# Power_sheet.net
KiCad netlist of a schematic drawn in Altium Designer
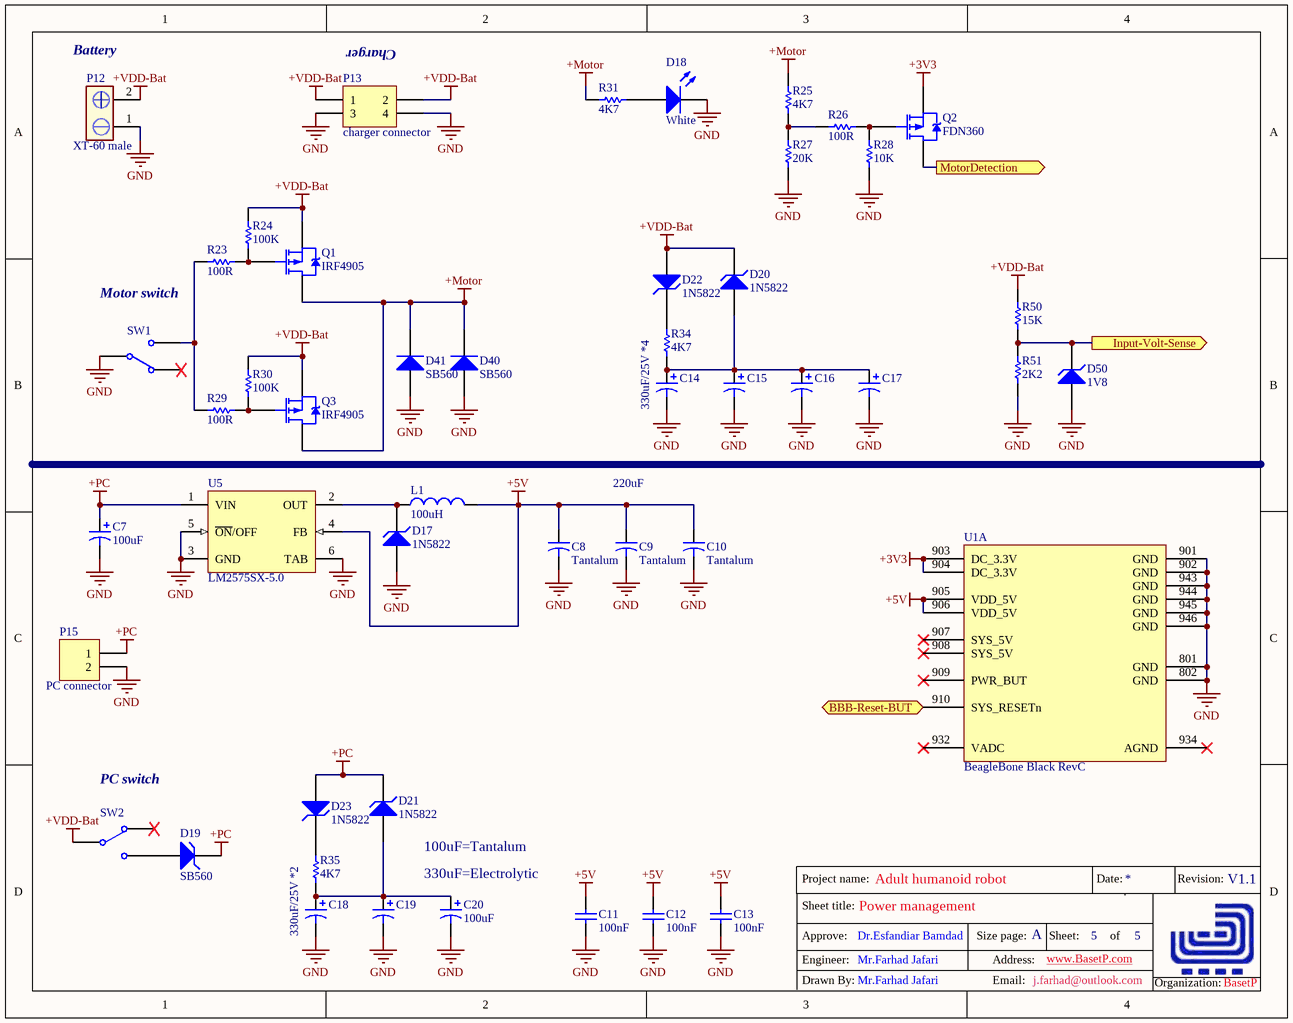
[diagram p0: Power sheet.SchDoc]

(export (version "E")
  (design (tool "Eeschema 10.0.6"))
  (components
    (comp (ref "C7")
      (value "100uF")
      (footprint "B")
      (description "Solid Aluminum Capacitor with Organic Semiconductor Electrolyte: 10uF, 10V, Bulk Pack")
      (fields (field (name "PUBLISHER") "Altium Limited"))
      (libsource (lib "Farhad_Library") (part "100uF/25V"))
    )
    (comp (ref "C8")
      (value "Tantalum")
      (footprint "tantalum E")
      (libsource (lib "Farhad_Library") (part "Tantalum"))
    )
    (comp (ref "C9")
      (value "Tantalum")
      (footprint "tantalum E")
      (libsource (lib "Farhad_Library") (part "Tantalum"))
    )
    (comp (ref "C10")
      (value "Tantalum")
      (footprint "tantalum E")
      (libsource (lib "Farhad_Library") (part "Tantalum"))
    )
    (comp (ref "C11")
      (value "100nF")
      (footprint "0805")
      (description "Ceramic Chip Capacitor - Standard")
      (fields (field (name "Comment") "C0805") (field (name "PUBLISHER") "Altium Limited"))
      (libsource (lib "KEMET Chip Capacitor") (part "C0805"))
    )
    (comp (ref "C12")
      (value "100nF")
      (footprint "0805")
      (description "Ceramic Chip Capacitor - Standard")
      (fields (field (name "Comment") "C0805") (field (name "PUBLISHER") "Altium Limited"))
      (libsource (lib "KEMET Chip Capacitor") (part "C0805"))
    )
    (comp (ref "C13")
      (value "100nF")
      (footprint "0805")
      (description "Ceramic Chip Capacitor - Standard")
      (fields (field (name "Comment") "C0805") (field (name "PUBLISHER") "Altium Limited"))
      (libsource (lib "KEMET Chip Capacitor") (part "C0805"))
    )
    (comp (ref "C14")
      (value "330uF/25V *4")
      (footprint "E'")
      (description "Solid Aluminum Capacitor with Organic Semiconductor Electrolyte: 100uF, 6.3V, Bulk Pack")
      (fields (field (name "PUBLISHER") "Altium Limited"))
      (libsource (lib "Farhad_Library") (part "330uF/25V"))
    )
    (comp (ref "C15")
      (value "330uF/25V")
      (footprint "E'")
      (description "Solid Aluminum Capacitor with Organic Semiconductor Electrolyte: 100uF, 6.3V, Bulk Pack")
      (fields (field (name "PUBLISHER") "Altium Limited"))
      (libsource (lib "Farhad_Library") (part "330uF/25V"))
    )
    (comp (ref "C16")
      (value "330uF/25V")
      (footprint "E'")
      (description "Solid Aluminum Capacitor with Organic Semiconductor Electrolyte: 100uF, 6.3V, Bulk Pack")
      (fields (field (name "PUBLISHER") "Altium Limited"))
      (libsource (lib "Farhad_Library") (part "330uF/25V"))
    )
    (comp (ref "C17")
      (value "330uF/25V")
      (footprint "E'")
      (description "Solid Aluminum Capacitor with Organic Semiconductor Electrolyte: 100uF, 6.3V, Bulk Pack")
      (fields (field (name "PUBLISHER") "Altium Limited"))
      (libsource (lib "Farhad_Library") (part "330uF/25V"))
    )
    (comp (ref "C18")
      (value "330uF/25V *2")
      (footprint "E'")
      (description "Solid Aluminum Capacitor with Organic Semiconductor Electrolyte: 100uF, 6.3V, Bulk Pack")
      (fields (field (name "PUBLISHER") "Altium Limited"))
      (libsource (lib "Farhad_Library") (part "330uF/25V"))
    )
    (comp (ref "C19")
      (value "`")
      (footprint "E'")
      (description "Solid Aluminum Capacitor with Organic Semiconductor Electrolyte: 100uF, 6.3V, Bulk Pack")
      (fields (field (name "PUBLISHER") "Altium Limited"))
      (libsource (lib "Farhad_Library") (part "330uF/25V"))
    )
    (comp (ref "C20")
      (value "100uF")
      (footprint "C5")
      (fields (field (name "PUBLISHER") "Altium Limited"))
      (libsource (lib "Vishay Sprague Tantalum Radial-Lead Capacitor") (part "STC68-15C5RM"))
    )
    (comp (ref "D17")
      (value "1N5822")
      (footprint "DL-41")
      (description "High-Voltage Power schottky Diode")
      (fields (field (name "PUBLISHER") "Altium Limited"))
      (libsource (lib "Farhad_Library") (part "1N5822"))
    )
    (comp (ref "D18")
      (value "White")
      (footprint "LED Red-0805")
      (description "High Performance Chip LED, Amber")
      (fields (field (name "PUBLISHER") "Altium Limited"))
      (libsource (lib "Farhad_Library") (part "LED-RED"))
    )
    (comp (ref "D19")
      (value "SB560")
      (footprint "DL-41")
      (description "High-Voltage Power schottky Diode")
      (fields (field (name "PUBLISHER") "Altium Limited"))
      (libsource (lib "Farhad_Library") (part "1N5822"))
    )
    (comp (ref "D20")
      (value "1N5822")
      (footprint "MELF")
      (description "High-Voltage Power Zener Diode")
      (fields (field (name "PUBLISHER") "Altium Limited"))
      (libsource (lib "Vishay Lite-On Discrete Diode") (part "ZMU100"))
    )
    (comp (ref "D21")
      (value "1N5822")
      (footprint "MELF")
      (description "High-Voltage Power Zener Diode")
      (fields (field (name "PUBLISHER") "Altium Limited"))
      (libsource (lib "Vishay Lite-On Discrete Diode") (part "ZMU100"))
    )
    (comp (ref "D22")
      (value "1N5822")
      (footprint "MELF")
      (description "High-Voltage Power Zener Diode")
      (fields (field (name "PUBLISHER") "Altium Limited"))
      (libsource (lib "Vishay Lite-On Discrete Diode") (part "ZMU100"))
    )
    (comp (ref "D23")
      (value "1N5822")
      (footprint "MELF")
      (description "High-Voltage Power Zener Diode")
      (fields (field (name "PUBLISHER") "Altium Limited"))
      (libsource (lib "Vishay Lite-On Discrete Diode") (part "ZMU100"))
    )
    (comp (ref "D40")
      (value "SB560")
      (footprint "DO-41")
      (description "1 Amp General Purpose Rectifier")
      (fields (field (name "PUBLISHER") "Altium Limited"))
      (libsource (lib "Farhad_Library") (part "Diode SB560"))
    )
    (comp (ref "D41")
      (value "SB560")
      (footprint "DO-41")
      (description "1 Amp General Purpose Rectifier")
      (fields (field (name "PUBLISHER") "Altium Limited"))
      (libsource (lib "Farhad_Library") (part "Diode SB560"))
    )
    (comp (ref "D50")
      (value "1V8")
      (footprint "MELF")
      (description "High-Voltage Power Zener Diode")
      (fields (field (name "PUBLISHER") "Altium Limited"))
      (libsource (lib "Vishay Lite-On Discrete Diode") (part "ZMU100"))
    )
    (comp (ref "L1")
      (value "100uH")
      (footprint "inductor coil")
      (description "Inductor coil  17mm * 9mm")
      (fields (field (name "PUBLISHER") "Altium Limited"))
      (libsource (lib "Farhad_Library") (part "Inductor coil"))
    )
    (comp (ref "P12")
      (value "XT-60 male")
      (footprint "XT-60 connector")
      (description "XT-60 connector male for battery")
      (libsource (lib "Farhad_Library") (part "XT-60 connector male"))
    )
    (comp (ref "P13")
      (value "charger connector")
      (footprint "connector 2*2")
      (description "Header, 4-Pin, 2X2 right angle")
      (fields (field (name "PUBLISHER") "Altium Limited"))
      (libsource (lib "Farhad_Library") (part "Header 2X2 right angle"))
    )
    (comp (ref "P15")
      (value "PC connector")
      (footprint "connector 1*2")
      (description "Header, 2-Pin right angle")
      (fields (field (name "PUBLISHER") "Altium Limited"))
      (libsource (lib "Farhad_Library") (part "Header 2 right angle"))
    )
    (comp (ref "Q1")
      (value "IRF4905")
      (footprint "TO-220AB")
      (description "HEXFET Power MOSFET")
      (fields (field (name "PUBLISHER") "Altium Limited"))
      (libsource (lib "IR Discrete MOSFET - Power") (part "IRF4905"))
    )
    (comp (ref "Q2")
      (value "FDN360")
      (footprint "SOT-23B_L")
      (description "Mosfet")
      (libsource (lib "Farhad_Library") (part "FDN360P"))
    )
    (comp (ref "Q3")
      (value "IRF4905")
      (footprint "TO-220AB")
      (description "HEXFET Power MOSFET")
      (fields (field (name "PUBLISHER") "Altium Limited"))
      (libsource (lib "IR Discrete MOSFET - Power") (part "IRF4905"))
    )
    (comp (ref "R23")
      (value "100R")
      (footprint "6-0805")
      (fields (field (name "PUBLISHER") "Altium Limited"))
      (libsource (lib "Panasonic Resistor") (part "ERJ6RS"))
    )
    (comp (ref "R24")
      (value "100K")
      (footprint "6-0805")
      (fields (field (name "PUBLISHER") "Altium Limited"))
      (libsource (lib "Panasonic Resistor") (part "ERJ6RS"))
    )
    (comp (ref "R25")
      (value "4K7")
      (footprint "6-0805")
      (fields (field (name "PUBLISHER") "Altium Limited"))
      (libsource (lib "Panasonic Resistor") (part "ERJ6RS"))
    )
    (comp (ref "R26")
      (value "100R")
      (footprint "6-0805")
      (fields (field (name "PUBLISHER") "Altium Limited"))
      (libsource (lib "Panasonic Resistor") (part "ERJ6RS"))
    )
    (comp (ref "R27")
      (value "20K")
      (footprint "6-0805")
      (fields (field (name "PUBLISHER") "Altium Limited"))
      (libsource (lib "Panasonic Resistor") (part "ERJ6RS"))
    )
    (comp (ref "R28")
      (value "10K")
      (footprint "6-0805")
      (fields (field (name "PUBLISHER") "Altium Limited"))
      (libsource (lib "Panasonic Resistor") (part "ERJ6RS"))
    )
    (comp (ref "R29")
      (value "100R")
      (footprint "6-0805")
      (fields (field (name "PUBLISHER") "Altium Limited"))
      (libsource (lib "Panasonic Resistor") (part "ERJ6RS"))
    )
    (comp (ref "R30")
      (value "100K")
      (footprint "6-0805")
      (fields (field (name "PUBLISHER") "Altium Limited"))
      (libsource (lib "Panasonic Resistor") (part "ERJ6RS"))
    )
    (comp (ref "R31")
      (value "4K7")
      (footprint "6-0805")
      (fields (field (name "PUBLISHER") "Altium Limited"))
      (libsource (lib "Panasonic Resistor") (part "ERJ6RS"))
    )
    (comp (ref "R34")
      (value "4K7")
      (footprint "8RB-1206")
      (fields (field (name "PUBLISHER") "Altium Limited"))
      (libsource (lib "Panasonic Resistor") (part "ERJ8RS"))
    )
    (comp (ref "R35")
      (value "4K7")
      (footprint "8RB-1206")
      (fields (field (name "PUBLISHER") "Altium Limited"))
      (libsource (lib "Panasonic Resistor") (part "ERJ8RS"))
    )
    (comp (ref "R50")
      (value "15K")
      (footprint "6-0805")
      (fields (field (name "PUBLISHER") "Altium Limited"))
      (libsource (lib "Panasonic Resistor") (part "ERJ6RS"))
    )
    (comp (ref "R51")
      (value "2K2")
      (footprint "6-0805")
      (fields (field (name "PUBLISHER") "Altium Limited"))
      (libsource (lib "Panasonic Resistor") (part "ERJ6RS"))
    )
    (comp (ref "SW1")
      (value "switch Red")
      (footprint "SW-power3A")
      (description "switch power black 3A/250VAC")
      (libsource (lib "Farhad_Library") (part "switch Power"))
    )
    (comp (ref "SW2")
      (value "switch Red")
      (footprint "SW-power3A")
      (description "switch power black 3A/250VAC")
      (libsource (lib "Farhad_Library") (part "switch Power"))
    )
    (comp (ref "U1")
      (value "BeagleBone Black RevC")
      (footprint "BBB-C")
      (libsource (lib "Farhad_Library") (part "BeagleBoneBlackRevC"))
    )
    (comp (ref "U5")
      (value "LM2575SX-5.0")
      (footprint "TS5B_N")
      (description "SIMPLE SWITCHER® 3A Step-Down Voltage Regulator, 5-pin TO-263")
      (fields
        (field (name "PARTNUMBER") "LM2576SX-5.0")
        (field (name "MANUFACTURER") "National Semiconductor")
        (field (name "PUBLISHER") "Altium Limited")
      )
      (libsource (lib "NSC Switcher") (part "LM2576SX-5.0"))
    )
  )
  (nets
    (net (code "1") (name "+3V3") (class "Default")
      (node (ref "Q2") (pin "2") (pinfunction "S_2") (pintype "passive"))
      (node (ref "U1") (pin "903") (pinfunction "DC_3.3V_903") (pintype "passive"))
      (node (ref "U1") (pin "904") (pinfunction "DC_3.3V_904") (pintype "passive"))
    )
    (net (code "2") (name "+5V") (class "Default")
      (node (ref "C10") (pin "1") (pinfunction "1_1") (pintype "passive"))
      (node (ref "C11") (pin "2") (pinfunction "2_2") (pintype "passive"))
      (node (ref "C12") (pin "2") (pinfunction "2_2") (pintype "passive"))
      (node (ref "C13") (pin "2") (pinfunction "2_2") (pintype "passive"))
      (node (ref "C8") (pin "1") (pinfunction "1_1") (pintype "passive"))
      (node (ref "C9") (pin "1") (pinfunction "1_1") (pintype "passive"))
      (node (ref "L1") (pin "2") (pinfunction "2_2") (pintype "passive"))
      (node (ref "U1") (pin "905") (pinfunction "VDD_5V_905") (pintype "passive"))
      (node (ref "U1") (pin "906") (pinfunction "VDD_5V_906") (pintype "passive"))
      (node (ref "U5") (pin "4") (pinfunction "FB_4") (pintype "input"))
    )
    (net (code "3") (name "+Motor") (class "Default")
      (node (ref "D40") (pin "2") (pinfunction "K_2") (pintype "passive"))
      (node (ref "D41") (pin "2") (pinfunction "K_2") (pintype "passive"))
      (node (ref "Q1") (pin "2") (pinfunction "D_2") (pintype "passive"))
      (node (ref "Q3") (pin "2") (pinfunction "D_2") (pintype "passive"))
      (node (ref "R25") (pin "2") (pinfunction "2_2") (pintype "passive"))
      (node (ref "R31") (pin "1") (pinfunction "1_1") (pintype "passive"))
    )
    (net (code "4") (name "+PC") (class "Default")
      (node (ref "C7") (pin "1") (pinfunction "1_1") (pintype "passive"))
      (node (ref "D19") (pin "2") (pinfunction "K_2") (pintype "passive"))
      (node (ref "D21") (pin "2") (pinfunction "K_2") (pintype "passive"))
      (node (ref "D23") (pin "1") (pinfunction "A_1") (pintype "passive"))
      (node (ref "P15") (pin "1") (pinfunction "1_1") (pintype "passive"))
      (node (ref "U5") (pin "1") (pinfunction "VIN_1") (pintype "power_in"))
    )
    (net (code "5") (name "+VDD-Bat") (class "Default")
      (node (ref "D20") (pin "2") (pinfunction "K_2") (pintype "passive"))
      (node (ref "D22") (pin "1") (pinfunction "A_1") (pintype "passive"))
      (node (ref "P12") (pin "2") (pinfunction "2_2") (pintype "passive"))
      (node (ref "P13") (pin "1") (pinfunction "1_1") (pintype "passive"))
      (node (ref "P13") (pin "2") (pinfunction "2_2") (pintype "passive"))
      (node (ref "Q1") (pin "3") (pinfunction "S_3") (pintype "passive"))
      (node (ref "Q3") (pin "3") (pinfunction "S_3") (pintype "passive"))
      (node (ref "R24") (pin "1") (pinfunction "1_1") (pintype "passive"))
      (node (ref "R30") (pin "2") (pinfunction "2_2") (pintype "passive"))
      (node (ref "R50") (pin "2") (pinfunction "2_2") (pintype "passive"))
      (node (ref "SW2") (pin "2") (pinfunction "COMMON1_2") (pintype "passive"))
    )
    (net (code "6") (name "/BBB-Reset-BUT") (class "Default")
      (node (ref "U1") (pin "910") (pinfunction "SYS_RESETn_910") (pintype "passive"))
    )
    (net (code "7") (name "/Input-Volt-Sense") (class "Default")
      (node (ref "D50") (pin "2") (pinfunction "K_2") (pintype "passive"))
      (node (ref "R50") (pin "1") (pinfunction "1_1") (pintype "passive"))
      (node (ref "R51") (pin "2") (pinfunction "2_2") (pintype "passive"))
    )
    (net (code "8") (name "/MotorDetection") (class "Default")
      (node (ref "Q2") (pin "3") (pinfunction "D_3") (pintype "passive"))
    )
    (net (code "9") (name "GND") (class "Default")
      (node (ref "C10") (pin "2") (pinfunction "2_2") (pintype "passive"))
      (node (ref "C11") (pin "1") (pinfunction "1_1") (pintype "passive"))
      (node (ref "C12") (pin "1") (pinfunction "1_1") (pintype "passive"))
      (node (ref "C13") (pin "1") (pinfunction "1_1") (pintype "passive"))
      (node (ref "C14") (pin "2") (pinfunction "2_2") (pintype "passive"))
      (node (ref "C15") (pin "2") (pinfunction "2_2") (pintype "passive"))
      (node (ref "C16") (pin "2") (pinfunction "2_2") (pintype "passive"))
      (node (ref "C17") (pin "2") (pinfunction "2_2") (pintype "passive"))
      (node (ref "C18") (pin "2") (pinfunction "2_2") (pintype "passive"))
      (node (ref "C19") (pin "2") (pinfunction "2_2") (pintype "passive"))
      (node (ref "C20") (pin "2") (pinfunction "2_2") (pintype "passive"))
      (node (ref "C7") (pin "2") (pinfunction "2_2") (pintype "passive"))
      (node (ref "C8") (pin "2") (pinfunction "2_2") (pintype "passive"))
      (node (ref "C9") (pin "2") (pinfunction "2_2") (pintype "passive"))
      (node (ref "D17") (pin "1") (pinfunction "A_1") (pintype "passive"))
      (node (ref "D18") (pin "2") (pinfunction "K_2") (pintype "passive"))
      (node (ref "D40") (pin "1") (pinfunction "A_1") (pintype "passive"))
      (node (ref "D41") (pin "1") (pinfunction "A_1") (pintype "passive"))
      (node (ref "D50") (pin "1") (pinfunction "A_1") (pintype "passive"))
      (node (ref "P12") (pin "1") (pinfunction "1_1") (pintype "passive"))
      (node (ref "P13") (pin "3") (pinfunction "3_3") (pintype "passive"))
      (node (ref "P13") (pin "4") (pinfunction "4_4") (pintype "passive"))
      (node (ref "P15") (pin "2") (pinfunction "2_2") (pintype "passive"))
      (node (ref "R27") (pin "1") (pinfunction "1_1") (pintype "passive"))
      (node (ref "R28") (pin "1") (pinfunction "1_1") (pintype "passive"))
      (node (ref "R51") (pin "1") (pinfunction "1_1") (pintype "passive"))
      (node (ref "SW1") (pin "2") (pinfunction "COMMON1_2") (pintype "passive"))
      (node (ref "U1") (pin "801") (pinfunction "GND_801") (pintype "passive"))
      (node (ref "U1") (pin "802") (pinfunction "GND_802") (pintype "passive"))
      (node (ref "U1") (pin "901") (pinfunction "GND_901") (pintype "passive"))
      (node (ref "U1") (pin "902") (pinfunction "GND_902") (pintype "passive"))
      (node (ref "U1") (pin "943") (pinfunction "GND_943") (pintype "passive"))
      (node (ref "U1") (pin "944") (pinfunction "GND_944") (pintype "passive"))
      (node (ref "U1") (pin "945") (pinfunction "GND_945") (pintype "passive"))
      (node (ref "U1") (pin "946") (pinfunction "GND_946") (pintype "passive"))
      (node (ref "U5") (pin "3") (pinfunction "GND_3") (pintype "power_in"))
      (node (ref "U5") (pin "5") (pinfunction "~{ON}/OFF_5") (pintype "input"))
      (node (ref "U5") (pin "6") (pinfunction "TAB_6") (pintype "power_in"))
    )
    (net (code "10") (name "Net-(D17-K)") (class "Default")
      (node (ref "D17") (pin "2") (pinfunction "K_2") (pintype "passive"))
      (node (ref "L1") (pin "1") (pinfunction "1_1") (pintype "passive"))
      (node (ref "U5") (pin "2") (pinfunction "OUT_2") (pintype "power_in"))
    )
    (net (code "11") (name "Net-(D18-A)") (class "Default")
      (node (ref "D18") (pin "1") (pinfunction "A_1") (pintype "passive"))
      (node (ref "R31") (pin "2") (pinfunction "2_2") (pintype "passive"))
    )
    (net (code "12") (name "Net-(D19-A)") (class "Default")
      (node (ref "D19") (pin "1") (pinfunction "A_1") (pintype "passive"))
      (node (ref "SW2") (pin "1") (pinfunction "NO1_1") (pintype "passive"))
    )
    (net (code "13") (name "Net-(D20-A)") (class "Default")
      (node (ref "C14") (pin "1") (pinfunction "1_1") (pintype "passive"))
      (node (ref "C15") (pin "1") (pinfunction "1_1") (pintype "passive"))
      (node (ref "C16") (pin "1") (pinfunction "1_1") (pintype "passive"))
      (node (ref "C17") (pin "1") (pinfunction "1_1") (pintype "passive"))
      (node (ref "D20") (pin "1") (pinfunction "A_1") (pintype "passive"))
      (node (ref "R34") (pin "1") (pinfunction "1_1") (pintype "passive"))
    )
    (net (code "14") (name "Net-(D21-A)") (class "Default")
      (node (ref "C18") (pin "1") (pinfunction "1_1") (pintype "passive"))
      (node (ref "C19") (pin "1") (pinfunction "1_1") (pintype "passive"))
      (node (ref "C20") (pin "1") (pinfunction "1_1") (pintype "passive"))
      (node (ref "D21") (pin "1") (pinfunction "A_1") (pintype "passive"))
      (node (ref "R35") (pin "1") (pinfunction "1_1") (pintype "passive"))
    )
    (net (code "15") (name "Net-(D22-K)") (class "Default")
      (node (ref "D22") (pin "2") (pinfunction "K_2") (pintype "passive"))
      (node (ref "R34") (pin "2") (pinfunction "2_2") (pintype "passive"))
    )
    (net (code "16") (name "Net-(D23-K)") (class "Default")
      (node (ref "D23") (pin "2") (pinfunction "K_2") (pintype "passive"))
      (node (ref "R35") (pin "2") (pinfunction "2_2") (pintype "passive"))
    )
    (net (code "17") (name "Net-(Q1-G)") (class "Default")
      (node (ref "Q1") (pin "1") (pinfunction "G_1") (pintype "passive"))
      (node (ref "R23") (pin "1") (pinfunction "1_1") (pintype "passive"))
      (node (ref "R24") (pin "2") (pinfunction "2_2") (pintype "passive"))
    )
    (net (code "18") (name "Net-(Q2-G)") (class "Default")
      (node (ref "Q2") (pin "1") (pinfunction "G_1") (pintype "passive"))
      (node (ref "R26") (pin "1") (pinfunction "1_1") (pintype "passive"))
      (node (ref "R28") (pin "2") (pinfunction "2_2") (pintype "passive"))
    )
    (net (code "19") (name "Net-(Q3-G)") (class "Default")
      (node (ref "Q3") (pin "1") (pinfunction "G_1") (pintype "passive"))
      (node (ref "R29") (pin "1") (pinfunction "1_1") (pintype "passive"))
      (node (ref "R30") (pin "1") (pinfunction "1_1") (pintype "passive"))
    )
    (net (code "20") (name "Net-(R25-Pad1)") (class "Default")
      (node (ref "R25") (pin "1") (pinfunction "1_1") (pintype "passive"))
      (node (ref "R26") (pin "2") (pinfunction "2_2") (pintype "passive"))
      (node (ref "R27") (pin "2") (pinfunction "2_2") (pintype "passive"))
    )
    (net (code "21") (name "Net-(SW1-NO1)") (class "Default")
      (node (ref "R23") (pin "2") (pinfunction "2_2") (pintype "passive"))
      (node (ref "R29") (pin "2") (pinfunction "2_2") (pintype "passive"))
      (node (ref "SW1") (pin "1") (pinfunction "NO1_1") (pintype "passive"))
    )
    (net (code "22") (name "unconnected-(SW1-NC1-Pad2)") (class "Default")
      (node (ref "SW1") (pin "2") (pinfunction "NC1_2") (pintype "passive"))
    )
    (net (code "23") (name "unconnected-(SW2-NC1-Pad2)") (class "Default")
      (node (ref "SW2") (pin "2") (pinfunction "NC1_2") (pintype "passive"))
    )
    (net (code "24") (name "unconnected-(U1A-AGND-Pad934)") (class "Default")
      (node (ref "U1") (pin "934") (pinfunction "AGND_934") (pintype "passive+no_connect"))
    )
    (net (code "25") (name "unconnected-(U1A-PWR_BUT-Pad909)") (class "Default")
      (node (ref "U1") (pin "909") (pinfunction "PWR_BUT_909") (pintype "passive+no_connect"))
    )
    (net (code "26") (name "unconnected-(U1A-SYS_5V-Pad907)") (class "Default")
      (node (ref "U1") (pin "907") (pinfunction "SYS_5V_907") (pintype "passive+no_connect"))
    )
    (net (code "27") (name "unconnected-(U1A-SYS_5V-Pad908)") (class "Default")
      (node (ref "U1") (pin "908") (pinfunction "SYS_5V_908") (pintype "passive+no_connect"))
    )
    (net (code "28") (name "unconnected-(U1A-VADC-Pad932)") (class "Default")
      (node (ref "U1") (pin "932") (pinfunction "VADC_932") (pintype "passive+no_connect"))
    )
  )
)
